# SBC_Gameduino.net
KiCad netlist of a schematic drawn in EAGLE
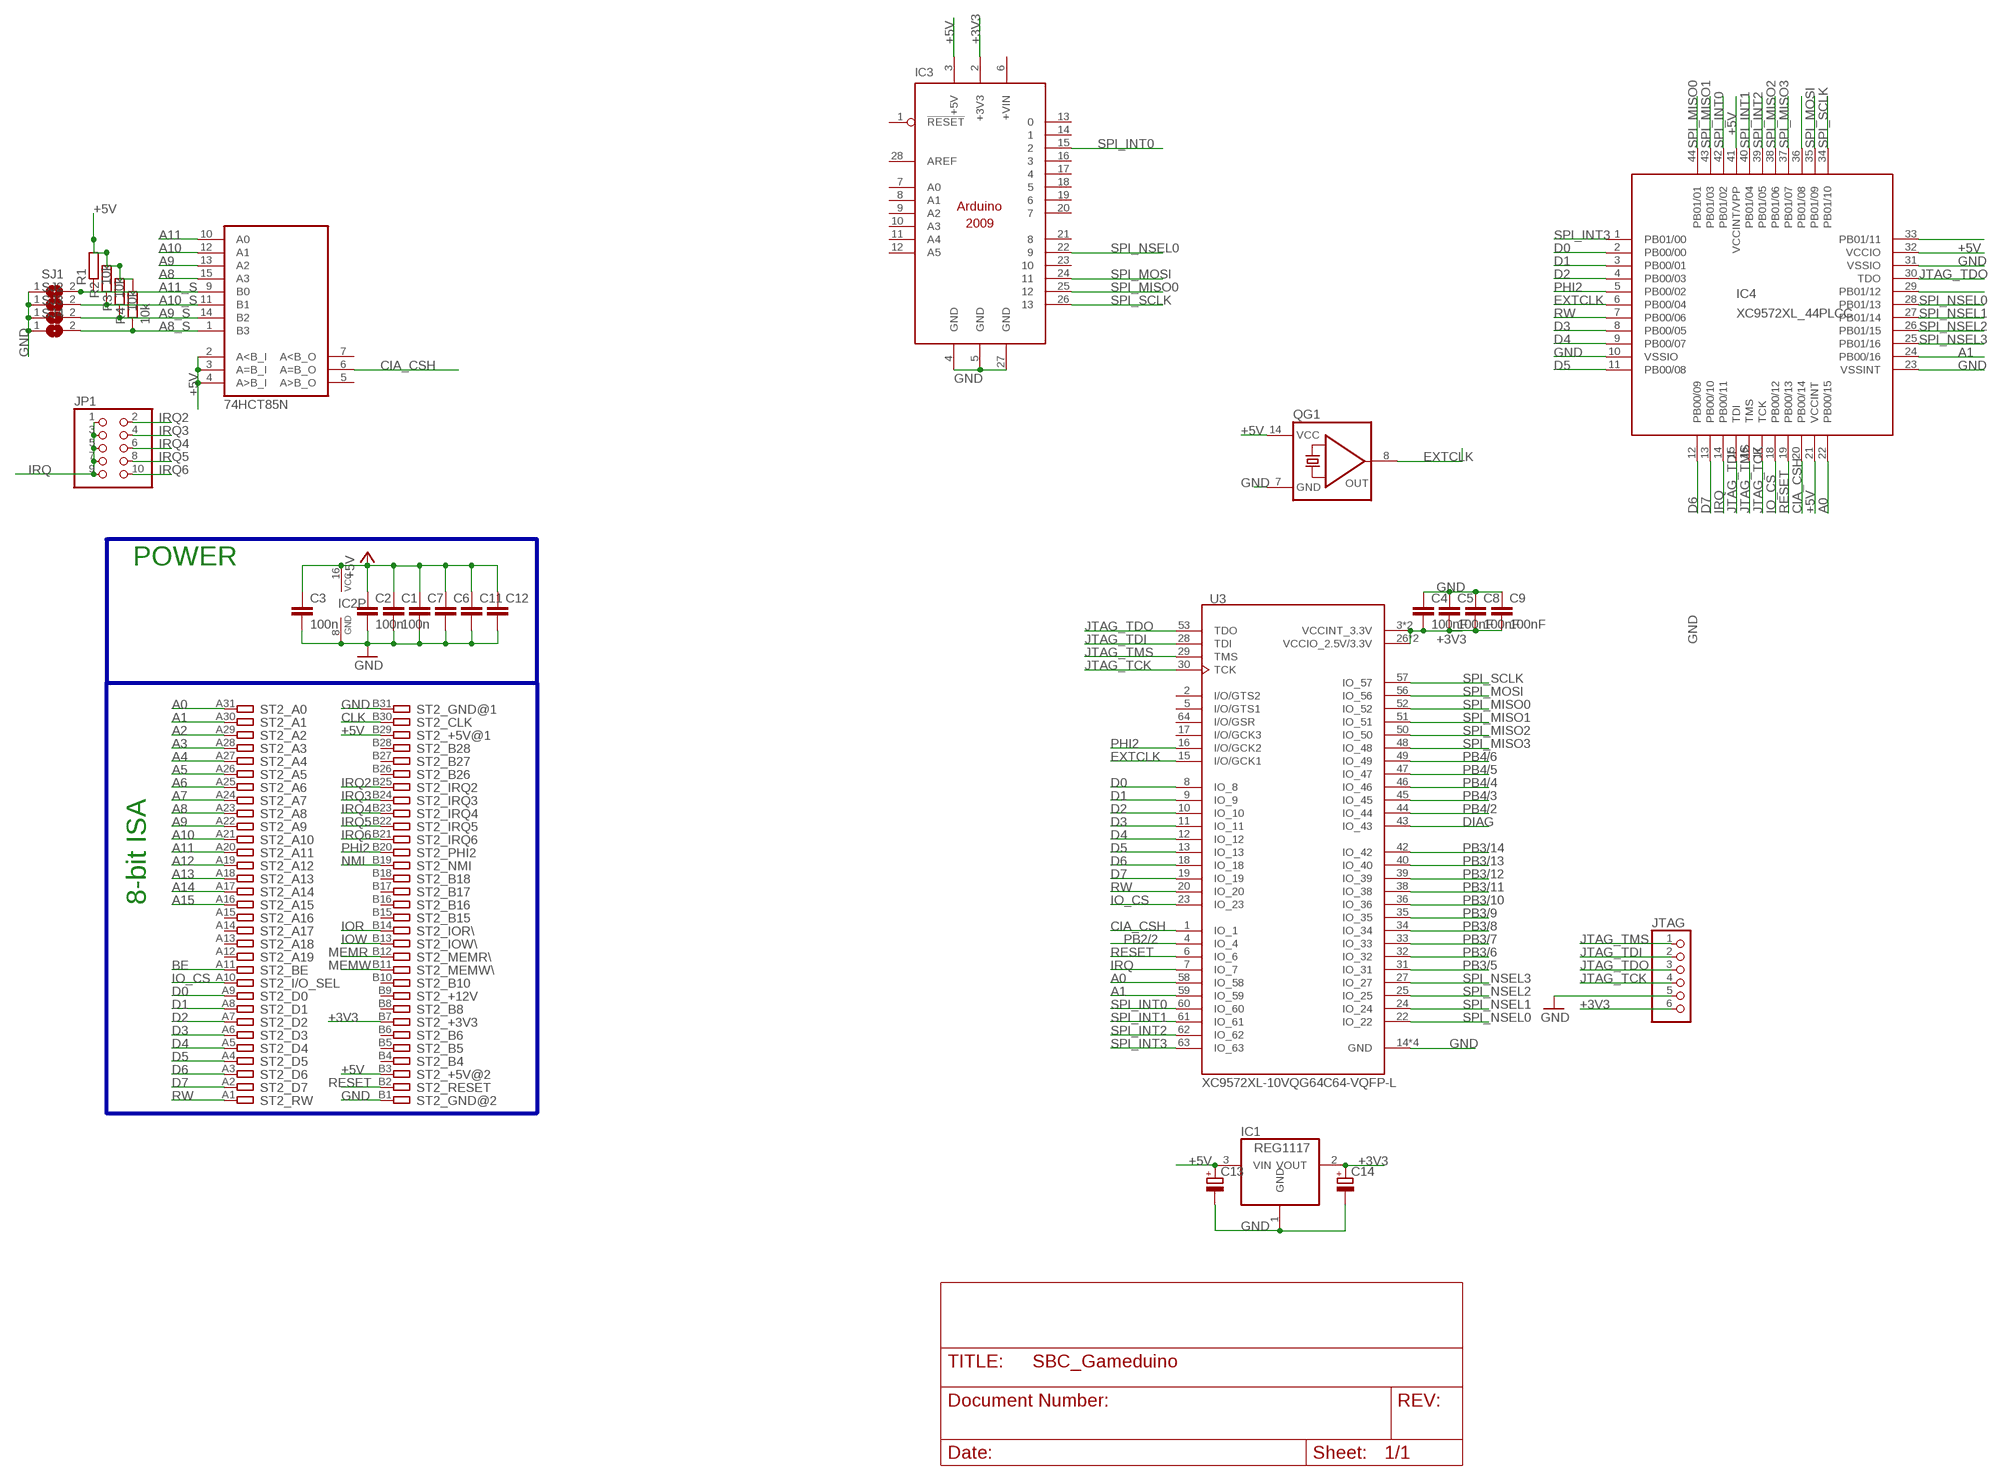
[diagram p0: schematic, sheet 1]

(export (version "E")
  (design (tool "Eeschema 10.0.6"))
  (components
    (comp (ref "C1")
      (value "100n")
      (footprint "eagle-import:C050-025X075")
      (libsource (lib "eagle-import") (part "C-EU050-025X075"))
    )
    (comp (ref "C2")
      (value "100n")
      (footprint "eagle-import:C050-025X075")
      (libsource (lib "eagle-import") (part "C-EU050-025X075"))
    )
    (comp (ref "C3")
      (value "100n")
      (footprint "eagle-import:C050-025X075")
      (libsource (lib "eagle-import") (part "C-EU050-025X075"))
    )
    (comp (ref "C4")
      (value "100nF")
      (footprint "eagle-import:C603")
      (libsource (lib "eagle-import") (part "CAPC603"))
    )
    (comp (ref "C5")
      (value "100nF")
      (footprint "eagle-import:C603")
      (libsource (lib "eagle-import") (part "CAPC603"))
    )
    (comp (ref "C6")
      (value "C-EU050-035X075")
      (footprint "eagle-import:C050-035X075")
      (libsource (lib "eagle-import") (part "rcl_334_C-EU050-035X075"))
    )
    (comp (ref "C7")
      (value "C-EU050-035X075")
      (footprint "eagle-import:C050-035X075")
      (libsource (lib "eagle-import") (part "rcl_334_C-EU050-035X075"))
    )
    (comp (ref "C8")
      (value "100nF")
      (footprint "eagle-import:C603")
      (libsource (lib "eagle-import") (part "CAPC603"))
    )
    (comp (ref "C9")
      (value "100nF")
      (footprint "eagle-import:C603")
      (libsource (lib "eagle-import") (part "CAPC603"))
    )
    (comp (ref "C11")
      (value "C-EU050-035X075")
      (footprint "eagle-import:C050-035X075")
      (libsource (lib "eagle-import") (part "rcl_334_C-EU050-035X075"))
    )
    (comp (ref "C12")
      (value "C-EU050-035X075")
      (footprint "eagle-import:C050-035X075")
      (libsource (lib "eagle-import") (part "rcl_334_C-EU050-035X075"))
    )
    (comp (ref "C13")
      (value "CPOL-EUE2.5-5")
      (footprint "eagle-import:E2,5-5")
      (libsource (lib "eagle-import") (part "CPOL-EUE2.5-5"))
    )
    (comp (ref "C14")
      (value "CPOL-EUE2.5-5")
      (footprint "eagle-import:E2,5-5")
      (libsource (lib "eagle-import") (part "CPOL-EUE2.5-5"))
    )
    (comp (ref "IC1")
      (value "REG1117")
      (footprint "eagle-import:SOT223")
      (libsource (lib "eagle-import") (part "REG1117"))
    )
    (comp (ref "IC2")
      (value "74HCT85N")
      (footprint "eagle-import:DIL16")
      (libsource (lib "eagle-import") (part "7485NHCT"))
    )
    (comp (ref "IC3")
      (value "ARDUINO2009_10")
      (footprint "eagle-import:ARDUINO2009")
      (libsource (lib "eagle-import") (part "ARDUINO2009_10"))
    )
    (comp (ref "IC4")
      (value "XC9572XL_44PLCC")
      (footprint "eagle-import:S44")
      (libsource (lib "eagle-import") (part "XC9536_44PLCCPLCC44_THT"))
    )
    (comp (ref "JP1")
      (value "PINHD-2X5")
      (footprint "eagle-import:2X05")
      (libsource (lib "eagle-import") (part "PINHD-2X5"))
    )
    (comp (ref "JTAG")
      (value "PINHD-1X6")
      (footprint "eagle-import:1X06")
      (libsource (lib "eagle-import") (part "PINHD-1X6"))
    )
    (comp (ref "QG1")
      (value "QG5860")
      (footprint "eagle-import:DIL14S")
      (libsource (lib "eagle-import") (part "QG5860"))
    )
    (comp (ref "R1")
      (value "10k")
      (footprint "eagle-import:0207_7")
      (libsource (lib "eagle-import") (part "R-EU_0207/7"))
    )
    (comp (ref "R2")
      (value "10k")
      (footprint "eagle-import:0207_7")
      (libsource (lib "eagle-import") (part "R-EU_0207/7"))
    )
    (comp (ref "R3")
      (value "10k")
      (footprint "eagle-import:0207_7")
      (libsource (lib "eagle-import") (part "R-EU_0207/7"))
    )
    (comp (ref "R4")
      (value "10k")
      (footprint "eagle-import:0207_7")
      (libsource (lib "eagle-import") (part "R-EU_0207/7"))
    )
    (comp (ref "SJ1") (value "SJ") (footprint "eagle-import:SJ") (libsource (lib "eagle-import") (part "SJ")))
    (comp (ref "SJ2") (value "SJ") (footprint "eagle-import:SJ") (libsource (lib "eagle-import") (part "SJ")))
    (comp (ref "SJ3") (value "SJ") (footprint "eagle-import:SJ") (libsource (lib "eagle-import") (part "SJ")))
    (comp (ref "SJ4") (value "SJ") (footprint "eagle-import:SJ") (libsource (lib "eagle-import") (part "SJ")))
    (comp (ref "ST2")
      (value "IBM8BIT_ISASHORT")
      (footprint "eagle-import:APP_2X32_SHORT")
      (libsource (lib "eagle-import") (part "IBM8BIT_ISASHORT"))
    )
    (comp (ref "U3")
      (value "XC9572XL-10VQG64C64-VQFP-L")
      (footprint "eagle-import:VQFP64")
      (fields
        (field (name "DIGIKEY_PARTNO") "122-1388-ND")
        (field (name "MANUFACTURER") "Xilinx Inc")
        (field (name "MPN") "XC9572XL-10VQG64C")
        (field (name "CREATED_BY") "PCBLayout.com")
      )
      (libsource (lib "eagle-import") (part "XC9572XL-10VQG64C64-VQFP-L"))
    )
  )
  (nets
    (net (code "1") (name "+5V") (class "Default")
      (node (ref "C1") (pin "1") (pinfunction "1_1") (pintype "passive"))
      (node (ref "C11") (pin "1") (pinfunction "1_1") (pintype "passive"))
      (node (ref "C12") (pin "1") (pinfunction "1_1") (pintype "passive"))
      (node (ref "C13") (pin "+") (pinfunction "+_+") (pintype "passive"))
      (node (ref "C2") (pin "1") (pinfunction "1_1") (pintype "passive"))
      (node (ref "C3") (pin "1") (pinfunction "1_1") (pintype "passive"))
      (node (ref "C6") (pin "1") (pinfunction "1_1") (pintype "passive"))
      (node (ref "C7") (pin "1") (pinfunction "1_1") (pintype "passive"))
      (node (ref "IC1") (pin "3") (pinfunction "VIN_3") (pintype "input"))
      (node (ref "IC2") (pin "16") (pinfunction "VCC_16") (pintype "power_in"))
      (node (ref "IC2") (pin "2") (pinfunction "A<B_I_2") (pintype "input"))
      (node (ref "IC2") (pin "3") (pinfunction "A=B_I_3") (pintype "input"))
      (node (ref "IC2") (pin "4") (pinfunction "A>B_I_4") (pintype "input"))
      (node (ref "IC3") (pin "3") (pinfunction "+5V_3") (pintype "power_in"))
      (node (ref "IC4") (pin "21") (pinfunction "VCCINT_21") (pintype "power_in"))
      (node (ref "IC4") (pin "32") (pinfunction "VCCIO_32") (pintype "power_in"))
      (node (ref "IC4") (pin "41") (pinfunction "VCCINT/VPP_41") (pintype "input"))
      (node (ref "QG1") (pin "14") (pinfunction "VCC_14") (pintype "power_in"))
      (node (ref "R1") (pin "2") (pinfunction "2_2") (pintype "passive"))
      (node (ref "R2") (pin "2") (pinfunction "2_2") (pintype "passive"))
      (node (ref "R3") (pin "2") (pinfunction "2_2") (pintype "passive"))
      (node (ref "R4") (pin "2") (pinfunction "2_2") (pintype "passive"))
      (node (ref "ST2") (pin "B29") (pinfunction "P_B29") (pintype "bidirectional"))
      (node (ref "ST2") (pin "B3") (pinfunction "P_B3") (pintype "bidirectional"))
    )
    (net (code "2") (name "/+3V3") (class "Default")
      (node (ref "C14") (pin "+") (pinfunction "+_+") (pintype "passive"))
      (node (ref "C4") (pin "2") (pinfunction "2_2") (pintype "passive"))
      (node (ref "C5") (pin "2") (pinfunction "2_2") (pintype "passive"))
      (node (ref "C8") (pin "2") (pinfunction "2_2") (pintype "passive"))
      (node (ref "C9") (pin "2") (pinfunction "2_2") (pintype "passive"))
      (node (ref "IC1") (pin "2") (pinfunction "VOUT_2") (pintype "output"))
      (node (ref "IC3") (pin "2") (pinfunction "+3V3_2") (pintype "power_in"))
      (node (ref "JTAG") (pin "6") (pinfunction "6_6") (pintype "passive"))
      (node (ref "ST2") (pin "B7") (pinfunction "P_B7") (pintype "bidirectional"))
      (node (ref "U3") (pin "26") (pinfunction "VCCIO_2.5V/3.3V_26") (pintype "power_in"))
      (node (ref "U3") (pin "3") (pinfunction "VCCINT_3.3V_3") (pintype "power_in"))
      (node (ref "U3") (pin "37") (pinfunction "VCCINT_3.3V_37") (pintype "power_in"))
      (node (ref "U3") (pin "55") (pinfunction "VCCIO_2.5V/3.3V_55") (pintype "power_in"))
    )
    (net (code "3") (name "/A0") (class "Default")
      (node (ref "IC4") (pin "22") (pinfunction "PB00/15_22") (pintype "bidirectional"))
      (node (ref "ST2") (pin "A31") (pinfunction "P_A31") (pintype "bidirectional"))
      (node (ref "U3") (pin "58") (pinfunction "IO_58_58") (pintype "bidirectional"))
    )
    (net (code "4") (name "/A1") (class "Default")
      (node (ref "IC4") (pin "24") (pinfunction "PB00/16_24") (pintype "bidirectional"))
      (node (ref "ST2") (pin "A30") (pinfunction "P_A30") (pintype "bidirectional"))
      (node (ref "U3") (pin "59") (pinfunction "IO_59_59") (pintype "bidirectional"))
    )
    (net (code "5") (name "/A2") (class "Default")
      (node (ref "ST2") (pin "A29") (pinfunction "P_A29") (pintype "bidirectional"))
    )
    (net (code "6") (name "/A3") (class "Default")
      (node (ref "ST2") (pin "A28") (pinfunction "P_A28") (pintype "bidirectional"))
    )
    (net (code "7") (name "/A4") (class "Default")
      (node (ref "ST2") (pin "A27") (pinfunction "P_A27") (pintype "bidirectional"))
    )
    (net (code "8") (name "/A5") (class "Default")
      (node (ref "ST2") (pin "A26") (pinfunction "P_A26") (pintype "bidirectional"))
    )
    (net (code "9") (name "/A6") (class "Default")
      (node (ref "ST2") (pin "A25") (pinfunction "P_A25") (pintype "bidirectional"))
    )
    (net (code "10") (name "/A7") (class "Default")
      (node (ref "ST2") (pin "A24") (pinfunction "P_A24") (pintype "bidirectional"))
    )
    (net (code "11") (name "/A8") (class "Default")
      (node (ref "IC2") (pin "15") (pinfunction "A3_15") (pintype "input"))
      (node (ref "ST2") (pin "A23") (pinfunction "P_A23") (pintype "bidirectional"))
    )
    (net (code "12") (name "/A8_S") (class "Default")
      (node (ref "IC2") (pin "1") (pinfunction "B3_1") (pintype "input"))
      (node (ref "R4") (pin "1") (pinfunction "1_1") (pintype "passive"))
      (node (ref "SJ4") (pin "2") (pinfunction "2_2") (pintype "passive"))
    )
    (net (code "13") (name "/A9") (class "Default")
      (node (ref "IC2") (pin "13") (pinfunction "A2_13") (pintype "input"))
      (node (ref "ST2") (pin "A22") (pinfunction "P_A22") (pintype "bidirectional"))
    )
    (net (code "14") (name "/A9_S") (class "Default")
      (node (ref "IC2") (pin "14") (pinfunction "B2_14") (pintype "input"))
      (node (ref "R3") (pin "1") (pinfunction "1_1") (pintype "passive"))
      (node (ref "SJ3") (pin "2") (pinfunction "2_2") (pintype "passive"))
    )
    (net (code "15") (name "/A10") (class "Default")
      (node (ref "IC2") (pin "12") (pinfunction "A1_12") (pintype "input"))
      (node (ref "ST2") (pin "A21") (pinfunction "P_A21") (pintype "bidirectional"))
    )
    (net (code "16") (name "/A10_S") (class "Default")
      (node (ref "IC2") (pin "11") (pinfunction "B1_11") (pintype "input"))
      (node (ref "R2") (pin "1") (pinfunction "1_1") (pintype "passive"))
      (node (ref "SJ2") (pin "2") (pinfunction "2_2") (pintype "passive"))
    )
    (net (code "17") (name "/A11") (class "Default")
      (node (ref "IC2") (pin "10") (pinfunction "A0_10") (pintype "input"))
      (node (ref "ST2") (pin "A20") (pinfunction "P_A20") (pintype "bidirectional"))
    )
    (net (code "18") (name "/A11_S") (class "Default")
      (node (ref "IC2") (pin "9") (pinfunction "B0_9") (pintype "input"))
      (node (ref "R1") (pin "1") (pinfunction "1_1") (pintype "passive"))
      (node (ref "SJ1") (pin "2") (pinfunction "2_2") (pintype "passive"))
    )
    (net (code "19") (name "/A12") (class "Default")
      (node (ref "ST2") (pin "A19") (pinfunction "P_A19") (pintype "bidirectional"))
    )
    (net (code "20") (name "/A13") (class "Default")
      (node (ref "ST2") (pin "A18") (pinfunction "P_A18") (pintype "bidirectional"))
    )
    (net (code "21") (name "/A14") (class "Default")
      (node (ref "ST2") (pin "A17") (pinfunction "P_A17") (pintype "bidirectional"))
    )
    (net (code "22") (name "/A15") (class "Default")
      (node (ref "ST2") (pin "A16") (pinfunction "P_A16") (pintype "bidirectional"))
    )
    (net (code "23") (name "/BE") (class "Default")
      (node (ref "ST2") (pin "A11") (pinfunction "P_A11") (pintype "bidirectional"))
    )
    (net (code "24") (name "/CIA_CSH") (class "Default")
      (node (ref "IC2") (pin "6") (pinfunction "A=B_O_6") (pintype "output"))
      (node (ref "IC4") (pin "20") (pinfunction "PB00/14_20") (pintype "bidirectional"))
      (node (ref "U3") (pin "1") (pinfunction "IO_1_1") (pintype "bidirectional"))
    )
    (net (code "25") (name "/CLK") (class "Default")
      (node (ref "ST2") (pin "B30") (pinfunction "P_B30") (pintype "bidirectional"))
    )
    (net (code "26") (name "/D0") (class "Default")
      (node (ref "IC4") (pin "2") (pinfunction "PB00/00_2") (pintype "bidirectional"))
      (node (ref "ST2") (pin "A9") (pinfunction "P_A9") (pintype "bidirectional"))
      (node (ref "U3") (pin "8") (pinfunction "IO_8_8") (pintype "bidirectional"))
    )
    (net (code "27") (name "/D1") (class "Default")
      (node (ref "IC4") (pin "3") (pinfunction "PB00/01_3") (pintype "bidirectional"))
      (node (ref "ST2") (pin "A8") (pinfunction "P_A8") (pintype "bidirectional"))
      (node (ref "U3") (pin "9") (pinfunction "IO_9_9") (pintype "bidirectional"))
    )
    (net (code "28") (name "/D2") (class "Default")
      (node (ref "IC4") (pin "4") (pinfunction "PB00/03_4") (pintype "bidirectional"))
      (node (ref "ST2") (pin "A7") (pinfunction "P_A7") (pintype "bidirectional"))
      (node (ref "U3") (pin "10") (pinfunction "IO_10_10") (pintype "bidirectional"))
    )
    (net (code "29") (name "/D3") (class "Default")
      (node (ref "IC4") (pin "8") (pinfunction "PB00/05_8") (pintype "bidirectional"))
      (node (ref "ST2") (pin "A6") (pinfunction "P_A6") (pintype "bidirectional"))
      (node (ref "U3") (pin "11") (pinfunction "IO_11_11") (pintype "bidirectional"))
    )
    (net (code "30") (name "/D4") (class "Default")
      (node (ref "IC4") (pin "9") (pinfunction "PB00/07_9") (pintype "bidirectional"))
      (node (ref "ST2") (pin "A5") (pinfunction "P_A5") (pintype "bidirectional"))
      (node (ref "U3") (pin "12") (pinfunction "IO_12_12") (pintype "bidirectional"))
    )
    (net (code "31") (name "/D5") (class "Default")
      (node (ref "IC4") (pin "11") (pinfunction "PB00/08_11") (pintype "bidirectional"))
      (node (ref "ST2") (pin "A4") (pinfunction "P_A4") (pintype "bidirectional"))
      (node (ref "U3") (pin "13") (pinfunction "IO_13_13") (pintype "bidirectional"))
    )
    (net (code "32") (name "/D6") (class "Default")
      (node (ref "IC4") (pin "12") (pinfunction "PB00/09_12") (pintype "bidirectional"))
      (node (ref "ST2") (pin "A3") (pinfunction "P_A3") (pintype "bidirectional"))
      (node (ref "U3") (pin "18") (pinfunction "IO_18_18") (pintype "bidirectional"))
    )
    (net (code "33") (name "/D7") (class "Default")
      (node (ref "IC4") (pin "13") (pinfunction "PB00/10_13") (pintype "bidirectional"))
      (node (ref "ST2") (pin "A2") (pinfunction "P_A2") (pintype "bidirectional"))
      (node (ref "U3") (pin "19") (pinfunction "IO_19_19") (pintype "bidirectional"))
    )
    (net (code "34") (name "/DIAG") (class "Default")
      (node (ref "U3") (pin "43") (pinfunction "IO_43_43") (pintype "bidirectional"))
    )
    (net (code "35") (name "/EXTCLK") (class "Default")
      (node (ref "IC4") (pin "6") (pinfunction "PB00/04_6") (pintype "bidirectional"))
      (node (ref "QG1") (pin "8") (pinfunction "OUT_8") (pintype "output"))
      (node (ref "U3") (pin "15") (pinfunction "I/O/GCK1_15") (pintype "bidirectional"))
    )
    (net (code "36") (name "/IOR") (class "Default")
      (node (ref "ST2") (pin "B14") (pinfunction "P_B14") (pintype "bidirectional"))
    )
    (net (code "37") (name "/IOW") (class "Default")
      (node (ref "ST2") (pin "B13") (pinfunction "P_B13") (pintype "bidirectional"))
    )
    (net (code "38") (name "/IO_CS") (class "Default")
      (node (ref "IC4") (pin "18") (pinfunction "PB00/12_18") (pintype "bidirectional"))
      (node (ref "ST2") (pin "A10") (pinfunction "P_A10") (pintype "bidirectional"))
      (node (ref "U3") (pin "23") (pinfunction "IO_23_23") (pintype "bidirectional"))
    )
    (net (code "39") (name "/IRQ") (class "Default")
      (node (ref "IC4") (pin "14") (pinfunction "PB00/11_14") (pintype "bidirectional"))
      (node (ref "JP1") (pin "1") (pinfunction "1_1") (pintype "passive"))
      (node (ref "JP1") (pin "3") (pinfunction "3_3") (pintype "passive"))
      (node (ref "JP1") (pin "5") (pinfunction "5_5") (pintype "passive"))
      (node (ref "JP1") (pin "7") (pinfunction "7_7") (pintype "passive"))
      (node (ref "JP1") (pin "9") (pinfunction "9_9") (pintype "passive"))
      (node (ref "U3") (pin "7") (pinfunction "IO_7_7") (pintype "bidirectional"))
    )
    (net (code "40") (name "/IRQ2") (class "Default")
      (node (ref "JP1") (pin "2") (pinfunction "2_2") (pintype "passive"))
      (node (ref "ST2") (pin "B25") (pinfunction "P_B25") (pintype "bidirectional"))
    )
    (net (code "41") (name "/IRQ3") (class "Default")
      (node (ref "JP1") (pin "4") (pinfunction "4_4") (pintype "passive"))
      (node (ref "ST2") (pin "B24") (pinfunction "P_B24") (pintype "bidirectional"))
    )
    (net (code "42") (name "/IRQ4") (class "Default")
      (node (ref "JP1") (pin "6") (pinfunction "6_6") (pintype "passive"))
      (node (ref "ST2") (pin "B23") (pinfunction "P_B23") (pintype "bidirectional"))
    )
    (net (code "43") (name "/IRQ5") (class "Default")
      (node (ref "JP1") (pin "8") (pinfunction "8_8") (pintype "passive"))
      (node (ref "ST2") (pin "B22") (pinfunction "P_B22") (pintype "bidirectional"))
    )
    (net (code "44") (name "/IRQ6") (class "Default")
      (node (ref "JP1") (pin "10") (pinfunction "10_10") (pintype "passive"))
      (node (ref "ST2") (pin "B21") (pinfunction "P_B21") (pintype "bidirectional"))
    )
    (net (code "45") (name "/JTAG_TCK") (class "Default")
      (node (ref "IC4") (pin "17") (pinfunction "TCK_17") (pintype "input"))
      (node (ref "JTAG") (pin "4") (pinfunction "4_4") (pintype "passive"))
      (node (ref "U3") (pin "30") (pinfunction "TCK_30") (pintype "input"))
    )
    (net (code "46") (name "/JTAG_TDI") (class "Default")
      (node (ref "IC4") (pin "15") (pinfunction "TDI_15") (pintype "input"))
      (node (ref "JTAG") (pin "2") (pinfunction "2_2") (pintype "passive"))
      (node (ref "U3") (pin "28") (pinfunction "TDI_28") (pintype "input"))
    )
    (net (code "47") (name "/JTAG_TDO") (class "Default")
      (node (ref "IC4") (pin "30") (pinfunction "TDO_30") (pintype "output"))
      (node (ref "JTAG") (pin "3") (pinfunction "3_3") (pintype "passive"))
      (node (ref "U3") (pin "53") (pinfunction "TDO_53") (pintype "input"))
    )
    (net (code "48") (name "/JTAG_TMS") (class "Default")
      (node (ref "IC4") (pin "16") (pinfunction "TMS_16") (pintype "input"))
      (node (ref "JTAG") (pin "1") (pinfunction "1_1") (pintype "passive"))
      (node (ref "U3") (pin "29") (pinfunction "TMS_29") (pintype "input"))
    )
    (net (code "49") (name "/MEMR") (class "Default")
      (node (ref "ST2") (pin "B12") (pinfunction "P_B12") (pintype "bidirectional"))
    )
    (net (code "50") (name "/MEMW") (class "Default")
      (node (ref "ST2") (pin "B11") (pinfunction "P_B11") (pintype "bidirectional"))
    )
    (net (code "51") (name "/NMI") (class "Default")
      (node (ref "ST2") (pin "B19") (pinfunction "P_B19") (pintype "bidirectional"))
    )
    (net (code "52") (name "/PB2{slash}2") (class "Default")
      (node (ref "U3") (pin "4") (pinfunction "IO_4_4") (pintype "bidirectional"))
    )
    (net (code "53") (name "/PB3{slash}5") (class "Default")
      (node (ref "U3") (pin "31") (pinfunction "IO_31_31") (pintype "bidirectional"))
    )
    (net (code "54") (name "/PB3{slash}6") (class "Default")
      (node (ref "U3") (pin "32") (pinfunction "IO_32_32") (pintype "bidirectional"))
    )
    (net (code "55") (name "/PB3{slash}7") (class "Default")
      (node (ref "U3") (pin "33") (pinfunction "IO_33_33") (pintype "bidirectional"))
    )
    (net (code "56") (name "/PB3{slash}8") (class "Default")
      (node (ref "U3") (pin "34") (pinfunction "IO_34_34") (pintype "bidirectional"))
    )
    (net (code "57") (name "/PB3{slash}9") (class "Default")
      (node (ref "U3") (pin "35") (pinfunction "IO_35_35") (pintype "bidirectional"))
    )
    (net (code "58") (name "/PB3{slash}10") (class "Default")
      (node (ref "U3") (pin "36") (pinfunction "IO_36_36") (pintype "bidirectional"))
    )
    (net (code "59") (name "/PB3{slash}11") (class "Default")
      (node (ref "U3") (pin "38") (pinfunction "IO_38_38") (pintype "bidirectional"))
    )
    (net (code "60") (name "/PB3{slash}12") (class "Default")
      (node (ref "U3") (pin "39") (pinfunction "IO_39_39") (pintype "bidirectional"))
    )
    (net (code "61") (name "/PB3{slash}13") (class "Default")
      (node (ref "U3") (pin "40") (pinfunction "IO_40_40") (pintype "bidirectional"))
    )
    (net (code "62") (name "/PB3{slash}14") (class "Default")
      (node (ref "U3") (pin "42") (pinfunction "IO_42_42") (pintype "bidirectional"))
    )
    (net (code "63") (name "/PB4{slash}2") (class "Default")
      (node (ref "U3") (pin "44") (pinfunction "IO_44_44") (pintype "bidirectional"))
    )
    (net (code "64") (name "/PB4{slash}3") (class "Default")
      (node (ref "U3") (pin "45") (pinfunction "IO_45_45") (pintype "bidirectional"))
    )
    (net (code "65") (name "/PB4{slash}4") (class "Default")
      (node (ref "U3") (pin "46") (pinfunction "IO_46_46") (pintype "bidirectional"))
    )
    (net (code "66") (name "/PB4{slash}5") (class "Default")
      (node (ref "U3") (pin "47") (pinfunction "IO_47_47") (pintype "bidirectional"))
    )
    (net (code "67") (name "/PB4{slash}6") (class "Default")
      (node (ref "U3") (pin "49") (pinfunction "IO_49_49") (pintype "bidirectional"))
    )
    (net (code "68") (name "/PHI2") (class "Default")
      (node (ref "IC4") (pin "5") (pinfunction "PB00/02_5") (pintype "bidirectional"))
      (node (ref "ST2") (pin "B20") (pinfunction "P_B20") (pintype "bidirectional"))
      (node (ref "U3") (pin "16") (pinfunction "I/O/GCK2_16") (pintype "bidirectional"))
    )
    (net (code "69") (name "/RESET") (class "Default")
      (node (ref "IC4") (pin "19") (pinfunction "PB00/13_19") (pintype "bidirectional"))
      (node (ref "ST2") (pin "B2") (pinfunction "P_B2") (pintype "bidirectional"))
      (node (ref "U3") (pin "6") (pinfunction "IO_6_6") (pintype "bidirectional"))
    )
    (net (code "70") (name "/RW") (class "Default")
      (node (ref "IC4") (pin "7") (pinfunction "PB00/06_7") (pintype "bidirectional"))
      (node (ref "ST2") (pin "A1") (pinfunction "P_A1") (pintype "bidirectional"))
      (node (ref "U3") (pin "20") (pinfunction "IO_20_20") (pintype "bidirectional"))
    )
    (net (code "71") (name "/SPI_INT0") (class "Default")
      (node (ref "IC3") (pin "15") (pinfunction "2_15") (pintype "bidirectional"))
      (node (ref "IC4") (pin "42") (pinfunction "PB01/02_42") (pintype "bidirectional"))
      (node (ref "U3") (pin "60") (pinfunction "IO_60_60") (pintype "bidirectional"))
    )
    (net (code "72") (name "/SPI_INT1") (class "Default")
      (node (ref "IC4") (pin "40") (pinfunction "PB01/04_40") (pintype "bidirectional"))
      (node (ref "U3") (pin "61") (pinfunction "IO_61_61") (pintype "bidirectional"))
    )
    (net (code "73") (name "/SPI_INT2") (class "Default")
      (node (ref "IC4") (pin "39") (pinfunction "PB01/05_39") (pintype "bidirectional"))
      (node (ref "U3") (pin "62") (pinfunction "IO_62_62") (pintype "bidirectional"))
    )
    (net (code "74") (name "/SPI_INT3") (class "Default")
      (node (ref "IC4") (pin "1") (pinfunction "PB01/00_1") (pintype "bidirectional"))
      (node (ref "U3") (pin "63") (pinfunction "IO_63_63") (pintype "bidirectional"))
    )
    (net (code "75") (name "/SPI_MISO0") (class "Default")
      (node (ref "IC3") (pin "25") (pinfunction "12_25") (pintype "bidirectional"))
      (node (ref "IC4") (pin "44") (pinfunction "PB01/01_44") (pintype "bidirectional"))
      (node (ref "U3") (pin "52") (pinfunction "IO_52_52") (pintype "bidirectional"))
    )
    (net (code "76") (name "/SPI_MISO1") (class "Default")
      (node (ref "IC4") (pin "43") (pinfunction "PB01/03_43") (pintype "bidirectional"))
      (node (ref "U3") (pin "51") (pinfunction "IO_51_51") (pintype "bidirectional"))
    )
    (net (code "77") (name "/SPI_MISO2") (class "Default")
      (node (ref "IC4") (pin "38") (pinfunction "PB01/06_38") (pintype "bidirectional"))
      (node (ref "U3") (pin "50") (pinfunction "IO_50_50") (pintype "bidirectional"))
    )
    (net (code "78") (name "/SPI_MISO3") (class "Default")
      (node (ref "IC4") (pin "37") (pinfunction "PB01/07_37") (pintype "bidirectional"))
      (node (ref "U3") (pin "48") (pinfunction "IO_48_48") (pintype "bidirectional"))
    )
    (net (code "79") (name "/SPI_MOSI") (class "Default")
      (node (ref "IC3") (pin "24") (pinfunction "11_24") (pintype "bidirectional"))
      (node (ref "IC4") (pin "35") (pinfunction "PB01/09_35") (pintype "bidirectional"))
      (node (ref "U3") (pin "56") (pinfunction "IO_56_56") (pintype "bidirectional"))
    )
    (net (code "80") (name "/SPI_NSEL0") (class "Default")
      (node (ref "IC3") (pin "22") (pinfunction "9_22") (pintype "bidirectional"))
      (node (ref "IC4") (pin "28") (pinfunction "PB01/13_28") (pintype "bidirectional"))
      (node (ref "U3") (pin "22") (pinfunction "IO_22_22") (pintype "bidirectional"))
    )
    (net (code "81") (name "/SPI_NSEL1") (class "Default")
      (node (ref "IC4") (pin "27") (pinfunction "PB01/14_27") (pintype "bidirectional"))
      (node (ref "U3") (pin "24") (pinfunction "IO_24_24") (pintype "bidirectional"))
    )
    (net (code "82") (name "/SPI_NSEL2") (class "Default")
      (node (ref "IC4") (pin "26") (pinfunction "PB01/15_26") (pintype "bidirectional"))
      (node (ref "U3") (pin "25") (pinfunction "IO_25_25") (pintype "bidirectional"))
    )
    (net (code "83") (name "/SPI_NSEL3") (class "Default")
      (node (ref "IC4") (pin "25") (pinfunction "PB01/16_25") (pintype "bidirectional"))
      (node (ref "U3") (pin "27") (pinfunction "IO_27_27") (pintype "bidirectional"))
    )
    (net (code "84") (name "/SPI_SCLK") (class "Default")
      (node (ref "IC3") (pin "26") (pinfunction "13_26") (pintype "bidirectional"))
      (node (ref "IC4") (pin "34") (pinfunction "PB01/10_34") (pintype "bidirectional"))
      (node (ref "U3") (pin "57") (pinfunction "IO_57_57") (pintype "bidirectional"))
    )
    (net (code "85") (name "GND") (class "Default")
      (node (ref "C1") (pin "2") (pinfunction "2_2") (pintype "passive"))
      (node (ref "C11") (pin "2") (pinfunction "2_2") (pintype "passive"))
      (node (ref "C12") (pin "2") (pinfunction "2_2") (pintype "passive"))
      (node (ref "C13") (pin "-") (pinfunction "-_-") (pintype "passive"))
      (node (ref "C14") (pin "-") (pinfunction "-_-") (pintype "passive"))
      (node (ref "C2") (pin "2") (pinfunction "2_2") (pintype "passive"))
      (node (ref "C3") (pin "2") (pinfunction "2_2") (pintype "passive"))
      (node (ref "C4") (pin "1") (pinfunction "1_1") (pintype "passive"))
      (node (ref "C5") (pin "1") (pinfunction "1_1") (pintype "passive"))
      (node (ref "C6") (pin "2") (pinfunction "2_2") (pintype "passive"))
      (node (ref "C7") (pin "2") (pinfunction "2_2") (pintype "passive"))
      (node (ref "C8") (pin "1") (pinfunction "1_1") (pintype "passive"))
      (node (ref "C9") (pin "1") (pinfunction "1_1") (pintype "passive"))
      (node (ref "IC1") (pin "1") (pinfunction "GND_1") (pintype "power_in"))
      (node (ref "IC2") (pin "8") (pinfunction "GND_8") (pintype "power_in"))
      (node (ref "IC3") (pin "27") (pinfunction "GND_27") (pintype "power_in"))
      (node (ref "IC3") (pin "4") (pinfunction "GND_4") (pintype "power_in"))
      (node (ref "IC3") (pin "5") (pinfunction "GND_5") (pintype "power_in"))
      (node (ref "IC4") (pin "10") (pinfunction "VSSIO_10") (pintype "power_in"))
      (node (ref "IC4") (pin "23") (pinfunction "VSSINT_23") (pintype "power_in"))
      (node (ref "IC4") (pin "31") (pinfunction "VSSIO_31") (pintype "power_in"))
      (node (ref "JTAG") (pin "5") (pinfunction "5_5") (pintype "passive"))
      (node (ref "QG1") (pin "7") (pinfunction "GND_7") (pintype "power_in"))
      (node (ref "SJ1") (pin "1") (pinfunction "1_1") (pintype "passive"))
      (node (ref "SJ2") (pin "1") (pinfunction "1_1") (pintype "passive"))
      (node (ref "SJ3") (pin "1") (pinfunction "1_1") (pintype "passive"))
      (node (ref "SJ4") (pin "1") (pinfunction "1_1") (pintype "passive"))
      (node (ref "ST2") (pin "B1") (pinfunction "P_B1") (pintype "bidirectional"))
      (node (ref "ST2") (pin "B31") (pinfunction "P_B31") (pintype "bidirectional"))
      (node (ref "U3") (pin "14") (pinfunction "GND_14") (pintype "power_in"))
      (node (ref "U3") (pin "21") (pinfunction "GND_21") (pintype "power_in"))
      (node (ref "U3") (pin "41") (pinfunction "GND_41") (pintype "power_in"))
      (node (ref "U3") (pin "54") (pinfunction "GND_54") (pintype "power_in"))
    )
    (net (code "86") (name "unconnected-(IC2A-A<B_O-Pad7)") (class "Default")
      (node (ref "IC2") (pin "7") (pinfunction "A<B_O_7") (pintype "output"))
    )
    (net (code "87") (name "unconnected-(IC2A-A>B_O-Pad5)") (class "Default")
      (node (ref "IC2") (pin "5") (pinfunction "A>B_O_5") (pintype "output"))
    )
    (net (code "88") (name "unconnected-(IC3-+VIN-Pad6)") (class "Default")
      (node (ref "IC3") (pin "6") (pinfunction "+VIN_6") (pintype "bidirectional"))
    )
    (net (code "89") (name "unconnected-(IC3-0-Pad13)") (class "Default")
      (node (ref "IC3") (pin "13") (pinfunction "0_13") (pintype "bidirectional"))
    )
    (net (code "90") (name "unconnected-(IC3-1-Pad14)") (class "Default")
      (node (ref "IC3") (pin "14") (pinfunction "1_14") (pintype "bidirectional"))
    )
    (net (code "91") (name "unconnected-(IC3-3-Pad16)") (class "Default")
      (node (ref "IC3") (pin "16") (pinfunction "3_16") (pintype "bidirectional"))
    )
    (net (code "92") (name "unconnected-(IC3-4-Pad17)") (class "Default")
      (node (ref "IC3") (pin "17") (pinfunction "4_17") (pintype "bidirectional"))
    )
    (net (code "93") (name "unconnected-(IC3-5-Pad18)") (class "Default")
      (node (ref "IC3") (pin "18") (pinfunction "5_18") (pintype "bidirectional"))
    )
    (net (code "94") (name "unconnected-(IC3-6-Pad19)") (class "Default")
      (node (ref "IC3") (pin "19") (pinfunction "6_19") (pintype "bidirectional"))
    )
    (net (code "95") (name "unconnected-(IC3-7-Pad20)") (class "Default")
      (node (ref "IC3") (pin "20") (pinfunction "7_20") (pintype "bidirectional"))
    )
    (net (code "96") (name "unconnected-(IC3-8-Pad21)") (class "Default")
      (node (ref "IC3") (pin "21") (pinfunction "8_21") (pintype "bidirectional"))
    )
    (net (code "97") (name "unconnected-(IC3-10-Pad23)") (class "Default")
      (node (ref "IC3") (pin "23") (pinfunction "10_23") (pintype "bidirectional"))
    )
    (net (code "98") (name "unconnected-(IC3-A0-Pad7)") (class "Default")
      (node (ref "IC3") (pin "7") (pinfunction "A0_7") (pintype "bidirectional"))
    )
    (net (code "99") (name "unconnected-(IC3-A1-Pad8)") (class "Default")
      (node (ref "IC3") (pin "8") (pinfunction "A1_8") (pintype "bidirectional"))
    )
    (net (code "100") (name "unconnected-(IC3-A2-Pad9)") (class "Default")
      (node (ref "IC3") (pin "9") (pinfunction "A2_9") (pintype "bidirectional"))
    )
    (net (code "101") (name "unconnected-(IC3-A3-Pad10)") (class "Default")
      (node (ref "IC3") (pin "10") (pinfunction "A3_10") (pintype "bidirectional"))
    )
    (net (code "102") (name "unconnected-(IC3-A4-Pad11)") (class "Default")
      (node (ref "IC3") (pin "11") (pinfunction "A4_11") (pintype "bidirectional"))
    )
    (net (code "103") (name "unconnected-(IC3-A5-Pad12)") (class "Default")
      (node (ref "IC3") (pin "12") (pinfunction "A5_12") (pintype "bidirectional"))
    )
    (net (code "104") (name "unconnected-(IC3-AREF-Pad28)") (class "Default")
      (node (ref "IC3") (pin "28") (pinfunction "AREF_28") (pintype "bidirectional"))
    )
    (net (code "105") (name "unconnected-(IC3-~{RESET}-Pad1)") (class "Default")
      (node (ref "IC3") (pin "1") (pinfunction "~{RESET}_1") (pintype "bidirectional"))
    )
    (net (code "106") (name "unconnected-(IC4-PB01{slash}08-Pad36)") (class "Default")
      (node (ref "IC4") (pin "36") (pinfunction "PB01/08_36") (pintype "bidirectional"))
    )
    (net (code "107") (name "unconnected-(IC4-PB01{slash}11-Pad33)") (class "Default")
      (node (ref "IC4") (pin "33") (pinfunction "PB01/11_33") (pintype "bidirectional"))
    )
    (net (code "108") (name "unconnected-(IC4-PB01{slash}12-Pad29)") (class "Default")
      (node (ref "IC4") (pin "29") (pinfunction "PB01/12_29") (pintype "bidirectional"))
    )
    (net (code "109") (name "unconnected-(ST2A-P-PadB9)") (class "Default")
      (node (ref "ST2") (pin "B9") (pinfunction "P_B9") (pintype "bidirectional"))
    )
    (net (code "110") (name "unconnected-(ST2AA-P-PadB16)") (class "Default")
      (node (ref "ST2") (pin "B16") (pinfunction "P_B16") (pintype "bidirectional"))
    )
    (net (code "111") (name "unconnected-(ST2AB-P-PadB17)") (class "Default")
      (node (ref "ST2") (pin "B17") (pinfunction "P_B17") (pintype "bidirectional"))
    )
    (net (code "112") (name "unconnected-(ST2AC-P-PadB18)") (class "Default")
      (node (ref "ST2") (pin "B18") (pinfunction "P_B18") (pintype "bidirectional"))
    )
    (net (code "113") (name "unconnected-(ST2AD-P-PadB26)") (class "Default")
      (node (ref "ST2") (pin "B26") (pinfunction "P_B26") (pintype "bidirectional"))
    )
    (net (code "114") (name "unconnected-(ST2AE-P-PadB27)") (class "Default")
      (node (ref "ST2") (pin "B27") (pinfunction "P_B27") (pintype "bidirectional"))
    )
    (net (code "115") (name "unconnected-(ST2AF-P-PadB28)") (class "Default")
      (node (ref "ST2") (pin "B28") (pinfunction "P_B28") (pintype "bidirectional"))
    )
    (net (code "116") (name "unconnected-(ST2AG-P-PadB4)") (class "Default")
      (node (ref "ST2") (pin "B4") (pinfunction "P_B4") (pintype "bidirectional"))
    )
    (net (code "117") (name "unconnected-(ST2AH-P-PadB5)") (class "Default")
      (node (ref "ST2") (pin "B5") (pinfunction "P_B5") (pintype "bidirectional"))
    )
    (net (code "118") (name "unconnected-(ST2AI-P-PadB6)") (class "Default")
      (node (ref "ST2") (pin "B6") (pinfunction "P_B6") (pintype "bidirectional"))
    )
    (net (code "119") (name "unconnected-(ST2AJ-P-PadB8)") (class "Default")
      (node (ref "ST2") (pin "B8") (pinfunction "P_B8") (pintype "bidirectional"))
    )
    (net (code "120") (name "unconnected-(ST2M-P-PadA15)") (class "Default")
      (node (ref "ST2") (pin "A15") (pinfunction "P_A15") (pintype "bidirectional"))
    )
    (net (code "121") (name "unconnected-(ST2N-P-PadA14)") (class "Default")
      (node (ref "ST2") (pin "A14") (pinfunction "P_A14") (pintype "bidirectional"))
    )
    (net (code "122") (name "unconnected-(ST2O-P-PadA13)") (class "Default")
      (node (ref "ST2") (pin "A13") (pinfunction "P_A13") (pintype "bidirectional"))
    )
    (net (code "123") (name "unconnected-(ST2P-P-PadA12)") (class "Default")
      (node (ref "ST2") (pin "A12") (pinfunction "P_A12") (pintype "bidirectional"))
    )
    (net (code "124") (name "unconnected-(ST2Y-P-PadB10)") (class "Default")
      (node (ref "ST2") (pin "B10") (pinfunction "P_B10") (pintype "bidirectional"))
    )
    (net (code "125") (name "unconnected-(ST2Z-P-PadB15)") (class "Default")
      (node (ref "ST2") (pin "B15") (pinfunction "P_B15") (pintype "bidirectional"))
    )
    (net (code "126") (name "unconnected-(U3-I{slash}O{slash}GCK3-Pad17)") (class "Default")
      (node (ref "U3") (pin "17") (pinfunction "I/O/GCK3_17") (pintype "bidirectional"))
    )
    (net (code "127") (name "unconnected-(U3-I{slash}O{slash}GSR-Pad64)") (class "Default")
      (node (ref "U3") (pin "64") (pinfunction "I/O/GSR_64") (pintype "bidirectional"))
    )
    (net (code "128") (name "unconnected-(U3-I{slash}O{slash}GTS1-Pad5)") (class "Default")
      (node (ref "U3") (pin "5") (pinfunction "I/O/GTS1_5") (pintype "bidirectional"))
    )
    (net (code "129") (name "unconnected-(U3-I{slash}O{slash}GTS2-Pad2)") (class "Default")
      (node (ref "U3") (pin "2") (pinfunction "I/O/GTS2_2") (pintype "bidirectional"))
    )
  )
)
